# 2021FM.net
KiCad netlist of a schematic drawn in Altium Designer
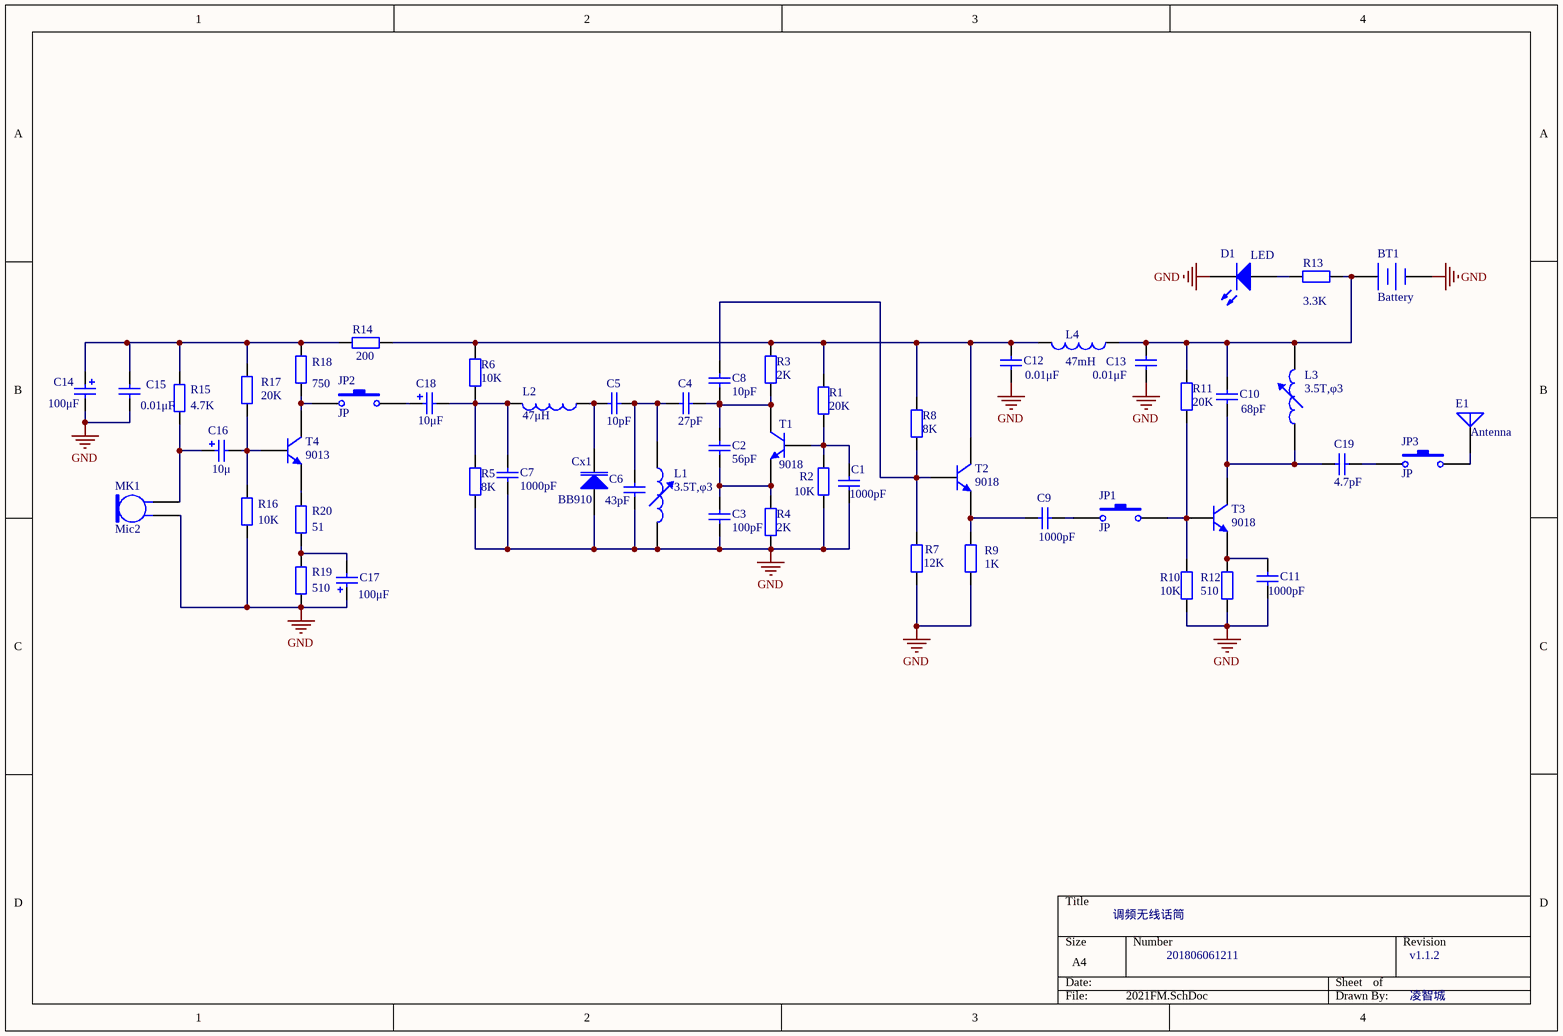
[diagram p0: 2021FM.SchDoc]

(export (version "E")
  (design (tool "Eeschema 10.0.6"))
  (components
    (comp (ref "BT1")
      (value "Battery")
      (footprint "BAT-2")
      (description "Multicell Battery")
      (fields (field (name "PUBLISHER") "Altium Limited"))
      (libsource (lib "Miscellaneous Devices") (part "Battery"))
    )
    (comp (ref "C1")
      (value "1000pF")
      (footprint "CAP")
      (description "Capacitor")
      (fields (field (name "Comment") "Cap") (field (name "PUBLISHER") "Altium Limited"))
      (libsource (lib "Miscellaneous Devices") (part "Cap"))
    )
    (comp (ref "C2")
      (value "56pF")
      (footprint "CAP")
      (description "Capacitor")
      (fields (field (name "Comment") "Cap") (field (name "PUBLISHER") "Altium Limited"))
      (libsource (lib "Miscellaneous Devices") (part "Cap"))
    )
    (comp (ref "C3")
      (value "100pF")
      (footprint "CAP")
      (description "Capacitor")
      (fields (field (name "Comment") "Cap") (field (name "PUBLISHER") "Altium Limited"))
      (libsource (lib "Miscellaneous Devices") (part "Cap"))
    )
    (comp (ref "C4")
      (value "27pF")
      (footprint "CAP")
      (description "Capacitor")
      (fields (field (name "Comment") "Cap") (field (name "PUBLISHER") "Altium Limited"))
      (libsource (lib "Miscellaneous Devices") (part "Cap"))
    )
    (comp (ref "C5")
      (value "10pF")
      (footprint "CAP")
      (description "Capacitor")
      (fields (field (name "Comment") "Cap") (field (name "PUBLISHER") "Altium Limited"))
      (libsource (lib "Miscellaneous Devices") (part "Cap"))
    )
    (comp (ref "C6")
      (value "43pF")
      (footprint "CAP")
      (description "Capacitor")
      (fields (field (name "Comment") "Cap") (field (name "PUBLISHER") "Altium Limited"))
      (libsource (lib "Miscellaneous Devices") (part "Cap"))
    )
    (comp (ref "C7")
      (value "1000pF")
      (footprint "CAP")
      (description "Capacitor")
      (fields (field (name "Comment") "Cap") (field (name "PUBLISHER") "Altium Limited"))
      (libsource (lib "Miscellaneous Devices") (part "Cap"))
    )
    (comp (ref "C8")
      (value "10pF")
      (footprint "CAP")
      (description "Capacitor")
      (fields (field (name "Comment") "Cap") (field (name "PUBLISHER") "Altium Limited"))
      (libsource (lib "Miscellaneous Devices") (part "Cap"))
    )
    (comp (ref "C9")
      (value "1000pF")
      (footprint "CAP")
      (description "Capacitor")
      (fields (field (name "Comment") "Cap") (field (name "PUBLISHER") "Altium Limited"))
      (libsource (lib "Miscellaneous Devices") (part "Cap"))
    )
    (comp (ref "C10")
      (value "68pF")
      (footprint "CAP")
      (description "Capacitor")
      (fields (field (name "Comment") "Cap") (field (name "PUBLISHER") "Altium Limited"))
      (libsource (lib "Miscellaneous Devices") (part "Cap"))
    )
    (comp (ref "C11")
      (value "1000pF")
      (footprint "CAP")
      (description "Capacitor")
      (fields (field (name "Comment") "Cap") (field (name "PUBLISHER") "Altium Limited"))
      (libsource (lib "Miscellaneous Devices") (part "Cap"))
    )
    (comp (ref "C12")
      (value "0.01μF")
      (footprint "CAP")
      (description "Capacitor")
      (fields (field (name "Comment") "Cap") (field (name "PUBLISHER") "Altium Limited"))
      (libsource (lib "Miscellaneous Devices") (part "Cap"))
    )
    (comp (ref "C13")
      (value "0.01μF")
      (footprint "CAP")
      (description "Capacitor")
      (fields (field (name "Comment") "Cap") (field (name "PUBLISHER") "Altium Limited"))
      (libsource (lib "Miscellaneous Devices") (part "Cap"))
    )
    (comp (ref "C14")
      (value "100μF")
      (footprint "CAP POL 100μF")
      (description "Polarized Capacitor (Axial)")
      (fields (field (name "Comment") "Cap Pol2") (field (name "PUBLISHER") "Altium Limited"))
      (libsource (lib "Miscellaneous Devices") (part "Cap Pol2"))
    )
    (comp (ref "C15")
      (value "0.01μF")
      (footprint "CAP")
      (description "Capacitor")
      (fields (field (name "Comment") "Cap") (field (name "PUBLISHER") "Altium Limited"))
      (libsource (lib "Miscellaneous Devices") (part "Cap"))
    )
    (comp (ref "C16")
      (value "10μ")
      (footprint "CAP POL 10μF")
      (description "Polarized Capacitor (Axial)")
      (fields (field (name "Comment") "Cap Pol2") (field (name "PUBLISHER") "Altium Limited"))
      (libsource (lib "Miscellaneous Devices") (part "Cap Pol2"))
    )
    (comp (ref "C17")
      (value "100μF")
      (footprint "CAP POL 100μF")
      (description "Polarized Capacitor (Axial)")
      (fields (field (name "Comment") "Cap Pol2") (field (name "PUBLISHER") "Altium Limited"))
      (libsource (lib "Miscellaneous Devices") (part "Cap Pol2"))
    )
    (comp (ref "C18")
      (value "10μF")
      (footprint "CAP POL 10μF")
      (description "Polarized Capacitor (Axial)")
      (fields (field (name "Comment") "Cap Pol2") (field (name "PUBLISHER") "Altium Limited"))
      (libsource (lib "Miscellaneous Devices") (part "Cap Pol2"))
    )
    (comp (ref "C19")
      (value "4.7pF")
      (footprint "CAP")
      (description "Capacitor")
      (fields (field (name "Comment") "Cap") (field (name "PUBLISHER") "Altium Limited"))
      (libsource (lib "Miscellaneous Devices") (part "Cap"))
    )
    (comp (ref "Cx1")
      (value "BB910")
      (footprint "D VACTOR")
      (description "Variable Capacitance Diode")
      (fields (field (name "PUBLISHER") "Altium Limited"))
      (libsource (lib "Miscellaneous Devices") (part "D Varactor"))
    )
    (comp (ref "D1")
      (value "LED")
      (footprint "LED")
      (description "Typical INFRARED GaAs LED")
      (fields (field (name "PUBLISHER") "Altium Limited"))
      (libsource (lib "Miscellaneous Devices") (part "LED0"))
    )
    (comp (ref "E1")
      (value "Antenna")
      (footprint "PIN1")
      (description "Generic Antenna")
      (fields (field (name "PUBLISHER") "Altium Limited"))
      (libsource (lib "Miscellaneous Devices") (part "Antenna"))
    )
    (comp (ref "JP1")
      (value "JP")
      (footprint "Jumper")
      (description "Switch")
      (fields (field (name "PUBLISHER") "Altium Limited"))
      (libsource (lib "Miscellaneous Devices") (part "SW-PB"))
    )
    (comp (ref "JP2")
      (value "JP")
      (footprint "Jumper")
      (description "Switch")
      (fields (field (name "PUBLISHER") "Altium Limited"))
      (libsource (lib "Miscellaneous Devices") (part "SW-PB"))
    )
    (comp (ref "JP3")
      (value "JP")
      (footprint "Jumper")
      (description "Switch")
      (fields (field (name "PUBLISHER") "Altium Limited"))
      (libsource (lib "Miscellaneous Devices") (part "SW-PB"))
    )
    (comp (ref "L1")
      (value "3.5T,φ3")
      (footprint "ADJ")
      (description "Adjustable Inductor")
      (fields (field (name "Comment") "Inductor Adj") (field (name "PUBLISHER") "Altium Limited"))
      (libsource (lib "") (part "Inductor Adj_1"))
    )
    (comp (ref "L2")
      (value "47μH")
      (footprint "INDUCTOR")
      (description "Inductor")
      (fields (field (name "PUBLISHER") "Altium Limited"))
      (libsource (lib "") (part "Inductor_1"))
    )
    (comp (ref "L3")
      (value "3.5T,φ3")
      (footprint "ADJ")
      (description "Adjustable Inductor")
      (fields (field (name "Comment") "Inductor Adj") (field (name "PUBLISHER") "Altium Limited"))
      (libsource (lib "Miscellaneous Devices") (part "Inductor Adj"))
    )
    (comp (ref "L4")
      (value "47mH")
      (footprint "INDUCTOR")
      (description "Inductor")
      (fields (field (name "PUBLISHER") "Altium Limited"))
      (libsource (lib "Miscellaneous Devices") (part "Inductor"))
    )
    (comp (ref "MK1")
      (value "Mic2")
      (footprint "Microphone")
      (description "Microphone")
      (fields (field (name "PUBLISHER") "Altium Limited"))
      (libsource (lib "Miscellaneous Devices") (part "Mic2"))
    )
    (comp (ref "R1")
      (value "20K")
      (footprint "RES")
      (description "Resistor")
      (fields (field (name "Comment") "Res2") (field (name "PUBLISHER") "Altium Limited"))
      (libsource (lib "Miscellaneous Devices") (part "Res2"))
    )
    (comp (ref "R2")
      (value "10K")
      (footprint "RES")
      (description "Resistor")
      (fields (field (name "Comment") "Res2") (field (name "PUBLISHER") "Altium Limited"))
      (libsource (lib "Miscellaneous Devices") (part "Res2"))
    )
    (comp (ref "R3")
      (value "2K")
      (footprint "RES")
      (description "Resistor")
      (fields (field (name "Comment") "Res2") (field (name "PUBLISHER") "Altium Limited"))
      (libsource (lib "Miscellaneous Devices") (part "Res2"))
    )
    (comp (ref "R4")
      (value "2K")
      (footprint "RES")
      (description "Resistor")
      (fields (field (name "Comment") "Res2") (field (name "PUBLISHER") "Altium Limited"))
      (libsource (lib "Miscellaneous Devices") (part "Res2"))
    )
    (comp (ref "R5")
      (value "8K")
      (footprint "RES")
      (description "Resistor")
      (fields (field (name "Comment") "Res2") (field (name "PUBLISHER") "Altium Limited"))
      (libsource (lib "Miscellaneous Devices") (part "Res2"))
    )
    (comp (ref "R6")
      (value "10K")
      (footprint "RES")
      (description "Resistor")
      (fields (field (name "Comment") "Res2") (field (name "PUBLISHER") "Altium Limited"))
      (libsource (lib "Miscellaneous Devices") (part "Res2"))
    )
    (comp (ref "R7")
      (value "12K")
      (footprint "RES")
      (description "Resistor")
      (fields (field (name "Comment") "Res2") (field (name "PUBLISHER") "Altium Limited"))
      (libsource (lib "") (part "Res2_1"))
    )
    (comp (ref "R8")
      (value "8K")
      (footprint "RES")
      (description "Resistor")
      (fields (field (name "Comment") "Res2") (field (name "PUBLISHER") "Altium Limited"))
      (libsource (lib "") (part "Res2_2"))
    )
    (comp (ref "R9")
      (value "1K")
      (footprint "RES")
      (description "Resistor")
      (fields (field (name "Comment") "Res2") (field (name "PUBLISHER") "Altium Limited"))
      (libsource (lib "") (part "Res2_2"))
    )
    (comp (ref "R10")
      (value "10K")
      (footprint "RES")
      (description "Resistor")
      (fields (field (name "Comment") "Res2") (field (name "PUBLISHER") "Altium Limited"))
      (libsource (lib "") (part "Res2_1"))
    )
    (comp (ref "R11")
      (value "20K")
      (footprint "RES")
      (description "Resistor")
      (fields (field (name "Comment") "Res2") (field (name "PUBLISHER") "Altium Limited"))
      (libsource (lib "") (part "Res2_1"))
    )
    (comp (ref "R12")
      (value "510")
      (footprint "RES")
      (description "Resistor")
      (fields (field (name "Comment") "Res2") (field (name "PUBLISHER") "Altium Limited"))
      (libsource (lib "") (part "Res2_1"))
    )
    (comp (ref "R13")
      (value "3.3K")
      (footprint "RES")
      (description "Resistor")
      (fields (field (name "Comment") "Res2") (field (name "PUBLISHER") "Altium Limited"))
      (libsource (lib "Miscellaneous Devices") (part "Res2"))
    )
    (comp (ref "R14")
      (value "200")
      (footprint "RES")
      (description "Resistor")
      (fields (field (name "Comment") "Res2") (field (name "PUBLISHER") "Altium Limited"))
      (libsource (lib "Miscellaneous Devices") (part "Res2"))
    )
    (comp (ref "R15")
      (value "4.7K")
      (footprint "RES")
      (description "Resistor")
      (fields (field (name "Comment") "Res2") (field (name "PUBLISHER") "Altium Limited"))
      (libsource (lib "") (part "Res2_1"))
    )
    (comp (ref "R16")
      (value "10K")
      (footprint "RES")
      (description "Resistor")
      (fields (field (name "Comment") "Res2") (field (name "PUBLISHER") "Altium Limited"))
      (libsource (lib "") (part "Res2_1"))
    )
    (comp (ref "R17")
      (value "20K")
      (footprint "RES")
      (description "Resistor")
      (fields (field (name "Comment") "Res2") (field (name "PUBLISHER") "Altium Limited"))
      (libsource (lib "") (part "Res2_1"))
    )
    (comp (ref "R18")
      (value "750")
      (footprint "RES")
      (description "Resistor")
      (fields (field (name "Comment") "Res2") (field (name "PUBLISHER") "Altium Limited"))
      (libsource (lib "") (part "Res2_1"))
    )
    (comp (ref "R19")
      (value "510")
      (footprint "RES")
      (description "Resistor")
      (fields (field (name "Comment") "Res2") (field (name "PUBLISHER") "Altium Limited"))
      (libsource (lib "") (part "Res2_1"))
    )
    (comp (ref "R20")
      (value "51")
      (footprint "RES")
      (description "Resistor")
      (fields (field (name "Comment") "Res2") (field (name "PUBLISHER") "Altium Limited"))
      (libsource (lib "") (part "Res2_1"))
    )
    (comp (ref "T1")
      (value "9018")
      (footprint "three")
      (description "NPN Bipolar Transistor")
      (fields (field (name "PUBLISHER") "Altium Limited"))
      (libsource (lib "Miscellaneous Devices") (part "NPN"))
    )
    (comp (ref "T2")
      (value "9018")
      (footprint "three")
      (description "NPN Bipolar Transistor")
      (fields (field (name "PUBLISHER") "Altium Limited"))
      (libsource (lib "Miscellaneous Devices") (part "NPN"))
    )
    (comp (ref "T3")
      (value "9018")
      (footprint "three")
      (description "NPN Bipolar Transistor")
      (fields (field (name "PUBLISHER") "Altium Limited"))
      (libsource (lib "Miscellaneous Devices") (part "NPN"))
    )
    (comp (ref "T4")
      (value "9013")
      (footprint "three")
      (description "NPN Bipolar Transistor")
      (fields (field (name "PUBLISHER") "Altium Limited"))
      (libsource (lib "Miscellaneous Devices") (part "NPN"))
    )
  )
  (nets
    (net (code "1") (name "GND") (class "Default")
      (node (ref "BT1") (pin "2") (pinfunction "-_2") (pintype "passive"))
      (node (ref "C1") (pin "1") (pinfunction "1_1") (pintype "passive"))
      (node (ref "C11") (pin "1") (pinfunction "1_1") (pintype "passive"))
      (node (ref "C12") (pin "1") (pinfunction "1_1") (pintype "passive"))
      (node (ref "C13") (pin "1") (pinfunction "1_1") (pintype "passive"))
      (node (ref "C14") (pin "2") (pinfunction "2_2") (pintype "passive"))
      (node (ref "C15") (pin "1") (pinfunction "1_1") (pintype "passive"))
      (node (ref "C17") (pin "1") (pinfunction "1_1") (pintype "passive"))
      (node (ref "C3") (pin "1") (pinfunction "1_1") (pintype "passive"))
      (node (ref "C6") (pin "1") (pinfunction "1_1") (pintype "passive"))
      (node (ref "C7") (pin "1") (pinfunction "1_1") (pintype "passive"))
      (node (ref "Cx1") (pin "2") (pinfunction "A_2") (pintype "passive"))
      (node (ref "D1") (pin "2") (pinfunction "K_2") (pintype "passive"))
      (node (ref "L1") (pin "1") (pinfunction "1_1") (pintype "passive"))
      (node (ref "MK1") (pin "1") (pinfunction "1_1") (pintype "passive"))
      (node (ref "R10") (pin "1") (pinfunction "1_1") (pintype "passive"))
      (node (ref "R12") (pin "1") (pinfunction "1_1") (pintype "passive"))
      (node (ref "R16") (pin "1") (pinfunction "1_1") (pintype "passive"))
      (node (ref "R19") (pin "1") (pinfunction "1_1") (pintype "passive"))
      (node (ref "R2") (pin "1") (pinfunction "1_1") (pintype "passive"))
      (node (ref "R4") (pin "1") (pinfunction "1_1") (pintype "passive"))
      (node (ref "R5") (pin "1") (pinfunction "1_1") (pintype "passive"))
      (node (ref "R7") (pin "1") (pinfunction "1_1") (pintype "passive"))
      (node (ref "R9") (pin "2") (pinfunction "2_2") (pintype "passive"))
    )
    (net (code "2") (name "Net-(BT1-+)") (class "Default")
      (node (ref "BT1") (pin "1") (pinfunction "+_1") (pintype "passive"))
      (node (ref "C10") (pin "2") (pinfunction "2_2") (pintype "passive"))
      (node (ref "C13") (pin "2") (pinfunction "2_2") (pintype "passive"))
      (node (ref "L3") (pin "2") (pinfunction "2_2") (pintype "passive"))
      (node (ref "L4") (pin "1") (pinfunction "1_1") (pintype "passive"))
      (node (ref "R11") (pin "2") (pinfunction "2_2") (pintype "passive"))
      (node (ref "R13") (pin "2") (pinfunction "2_2") (pintype "passive"))
    )
    (net (code "3") (name "Net-(C4-Pad2)") (class "Default")
      (node (ref "C4") (pin "2") (pinfunction "2_2") (pintype "passive"))
      (node (ref "C5") (pin "2") (pinfunction "2_2") (pintype "passive"))
      (node (ref "C6") (pin "2") (pinfunction "2_2") (pintype "passive"))
      (node (ref "L1") (pin "2") (pinfunction "2_2") (pintype "passive"))
    )
    (net (code "4") (name "Net-(C9-Pad1)") (class "Default")
      (node (ref "C9") (pin "1") (pinfunction "1_1") (pintype "passive"))
      (node (ref "JP1") (pin "1") (pinfunction "1_1") (pintype "passive"))
    )
    (net (code "5") (name "Net-(C14-Pad1)") (class "Default")
      (node (ref "C14") (pin "1") (pinfunction "1_1") (pintype "passive"))
      (node (ref "C15") (pin "2") (pinfunction "2_2") (pintype "passive"))
      (node (ref "R14") (pin "1") (pinfunction "1_1") (pintype "passive"))
      (node (ref "R15") (pin "2") (pinfunction "2_2") (pintype "passive"))
      (node (ref "R17") (pin "2") (pinfunction "2_2") (pintype "passive"))
      (node (ref "R18") (pin "2") (pinfunction "2_2") (pintype "passive"))
    )
    (net (code "6") (name "Net-(C16-Pad1)") (class "Default")
      (node (ref "C16") (pin "1") (pinfunction "1_1") (pintype "passive"))
      (node (ref "MK1") (pin "2") (pinfunction "2_2") (pintype "passive"))
      (node (ref "R15") (pin "1") (pinfunction "1_1") (pintype "passive"))
    )
    (net (code "7") (name "Net-(C17-Pad2)") (class "Default")
      (node (ref "C17") (pin "2") (pinfunction "2_2") (pintype "passive"))
      (node (ref "R19") (pin "2") (pinfunction "2_2") (pintype "passive"))
      (node (ref "R20") (pin "1") (pinfunction "1_1") (pintype "passive"))
    )
    (net (code "8") (name "Net-(C18-Pad1)") (class "Default")
      (node (ref "C18") (pin "1") (pinfunction "1_1") (pintype "passive"))
      (node (ref "JP2") (pin "2") (pinfunction "2_2") (pintype "passive"))
    )
    (net (code "9") (name "Net-(C18-Pad2)") (class "Default")
      (node (ref "C18") (pin "2") (pinfunction "2_2") (pintype "passive"))
      (node (ref "C7") (pin "2") (pinfunction "2_2") (pintype "passive"))
      (node (ref "L2") (pin "1") (pinfunction "1_1") (pintype "passive"))
      (node (ref "R5") (pin "2") (pinfunction "2_2") (pintype "passive"))
      (node (ref "R6") (pin "1") (pinfunction "1_1") (pintype "passive"))
    )
    (net (code "10") (name "Net-(C19-Pad1)") (class "Default")
      (node (ref "C19") (pin "1") (pinfunction "1_1") (pintype "passive"))
      (node (ref "JP3") (pin "1") (pinfunction "1_1") (pintype "passive"))
    )
    (net (code "11") (name "Net-(Cx1-K)") (class "Default")
      (node (ref "C5") (pin "1") (pinfunction "1_1") (pintype "passive"))
      (node (ref "Cx1") (pin "1") (pinfunction "K_1") (pintype "passive"))
      (node (ref "L2") (pin "2") (pinfunction "2_2") (pintype "passive"))
    )
    (net (code "12") (name "Net-(D1-A)") (class "Default")
      (node (ref "D1") (pin "1") (pinfunction "A_1") (pintype "passive"))
      (node (ref "R13") (pin "1") (pinfunction "1_1") (pintype "passive"))
    )
    (net (code "13") (name "Net-(E1-A)") (class "Default")
      (node (ref "E1") (pin "1") (pinfunction "A_1") (pintype "passive"))
      (node (ref "JP3") (pin "2") (pinfunction "2_2") (pintype "passive"))
    )
    (net (code "14") (name "Net-(T1-B)") (class "Default")
      (node (ref "C1") (pin "2") (pinfunction "2_2") (pintype "passive"))
      (node (ref "R1") (pin "1") (pinfunction "1_1") (pintype "passive"))
      (node (ref "R2") (pin "2") (pinfunction "2_2") (pintype "passive"))
      (node (ref "T1") (pin "2") (pinfunction "B_2") (pintype "passive"))
    )
    (net (code "15") (name "Net-(T1-C)") (class "Default")
      (node (ref "C2") (pin "2") (pinfunction "2_2") (pintype "passive"))
      (node (ref "C4") (pin "1") (pinfunction "1_1") (pintype "passive"))
      (node (ref "C8") (pin "2") (pinfunction "2_2") (pintype "passive"))
      (node (ref "R3") (pin "1") (pinfunction "1_1") (pintype "passive"))
      (node (ref "T1") (pin "1") (pinfunction "C_1") (pintype "passive"))
    )
    (net (code "16") (name "Net-(T1-E)") (class "Default")
      (node (ref "C2") (pin "1") (pinfunction "1_1") (pintype "passive"))
      (node (ref "C3") (pin "2") (pinfunction "2_2") (pintype "passive"))
      (node (ref "R4") (pin "2") (pinfunction "2_2") (pintype "passive"))
      (node (ref "T1") (pin "3") (pinfunction "E_3") (pintype "passive"))
    )
    (net (code "17") (name "Net-(T2-B)") (class "Default")
      (node (ref "C8") (pin "1") (pinfunction "1_1") (pintype "passive"))
      (node (ref "R7") (pin "2") (pinfunction "2_2") (pintype "passive"))
      (node (ref "R8") (pin "2") (pinfunction "2_2") (pintype "passive"))
      (node (ref "T2") (pin "2") (pinfunction "B_2") (pintype "passive"))
    )
    (net (code "18") (name "Net-(T2-C)") (class "Default")
      (node (ref "C12") (pin "2") (pinfunction "2_2") (pintype "passive"))
      (node (ref "L4") (pin "2") (pinfunction "2_2") (pintype "passive"))
      (node (ref "R1") (pin "2") (pinfunction "2_2") (pintype "passive"))
      (node (ref "R14") (pin "2") (pinfunction "2_2") (pintype "passive"))
      (node (ref "R3") (pin "2") (pinfunction "2_2") (pintype "passive"))
      (node (ref "R6") (pin "2") (pinfunction "2_2") (pintype "passive"))
      (node (ref "R8") (pin "1") (pinfunction "1_1") (pintype "passive"))
      (node (ref "T2") (pin "1") (pinfunction "C_1") (pintype "passive"))
    )
    (net (code "19") (name "Net-(T2-E)") (class "Default")
      (node (ref "C9") (pin "2") (pinfunction "2_2") (pintype "passive"))
      (node (ref "R9") (pin "1") (pinfunction "1_1") (pintype "passive"))
      (node (ref "T2") (pin "3") (pinfunction "E_3") (pintype "passive"))
    )
    (net (code "20") (name "Net-(T3-B)") (class "Default")
      (node (ref "JP1") (pin "2") (pinfunction "2_2") (pintype "passive"))
      (node (ref "R10") (pin "2") (pinfunction "2_2") (pintype "passive"))
      (node (ref "R11") (pin "1") (pinfunction "1_1") (pintype "passive"))
      (node (ref "T3") (pin "2") (pinfunction "B_2") (pintype "passive"))
    )
    (net (code "21") (name "Net-(T3-C)") (class "Default")
      (node (ref "C10") (pin "1") (pinfunction "1_1") (pintype "passive"))
      (node (ref "C19") (pin "2") (pinfunction "2_2") (pintype "passive"))
      (node (ref "L3") (pin "1") (pinfunction "1_1") (pintype "passive"))
      (node (ref "T3") (pin "1") (pinfunction "C_1") (pintype "passive"))
    )
    (net (code "22") (name "Net-(T3-E)") (class "Default")
      (node (ref "C11") (pin "2") (pinfunction "2_2") (pintype "passive"))
      (node (ref "R12") (pin "2") (pinfunction "2_2") (pintype "passive"))
      (node (ref "T3") (pin "3") (pinfunction "E_3") (pintype "passive"))
    )
    (net (code "23") (name "Net-(T4-B)") (class "Default")
      (node (ref "C16") (pin "2") (pinfunction "2_2") (pintype "passive"))
      (node (ref "R16") (pin "2") (pinfunction "2_2") (pintype "passive"))
      (node (ref "R17") (pin "1") (pinfunction "1_1") (pintype "passive"))
      (node (ref "T4") (pin "2") (pinfunction "B_2") (pintype "passive"))
    )
    (net (code "24") (name "Net-(T4-C)") (class "Default")
      (node (ref "JP2") (pin "1") (pinfunction "1_1") (pintype "passive"))
      (node (ref "R18") (pin "1") (pinfunction "1_1") (pintype "passive"))
      (node (ref "T4") (pin "1") (pinfunction "C_1") (pintype "passive"))
    )
    (net (code "25") (name "Net-(T4-E)") (class "Default")
      (node (ref "R20") (pin "2") (pinfunction "2_2") (pintype "passive"))
      (node (ref "T4") (pin "3") (pinfunction "E_3") (pintype "passive"))
    )
  )
)
